# SCH_MR2-reactive-led-system-new-audio-sy.net
KiCad netlist of a schematic drawn in EasyEDA
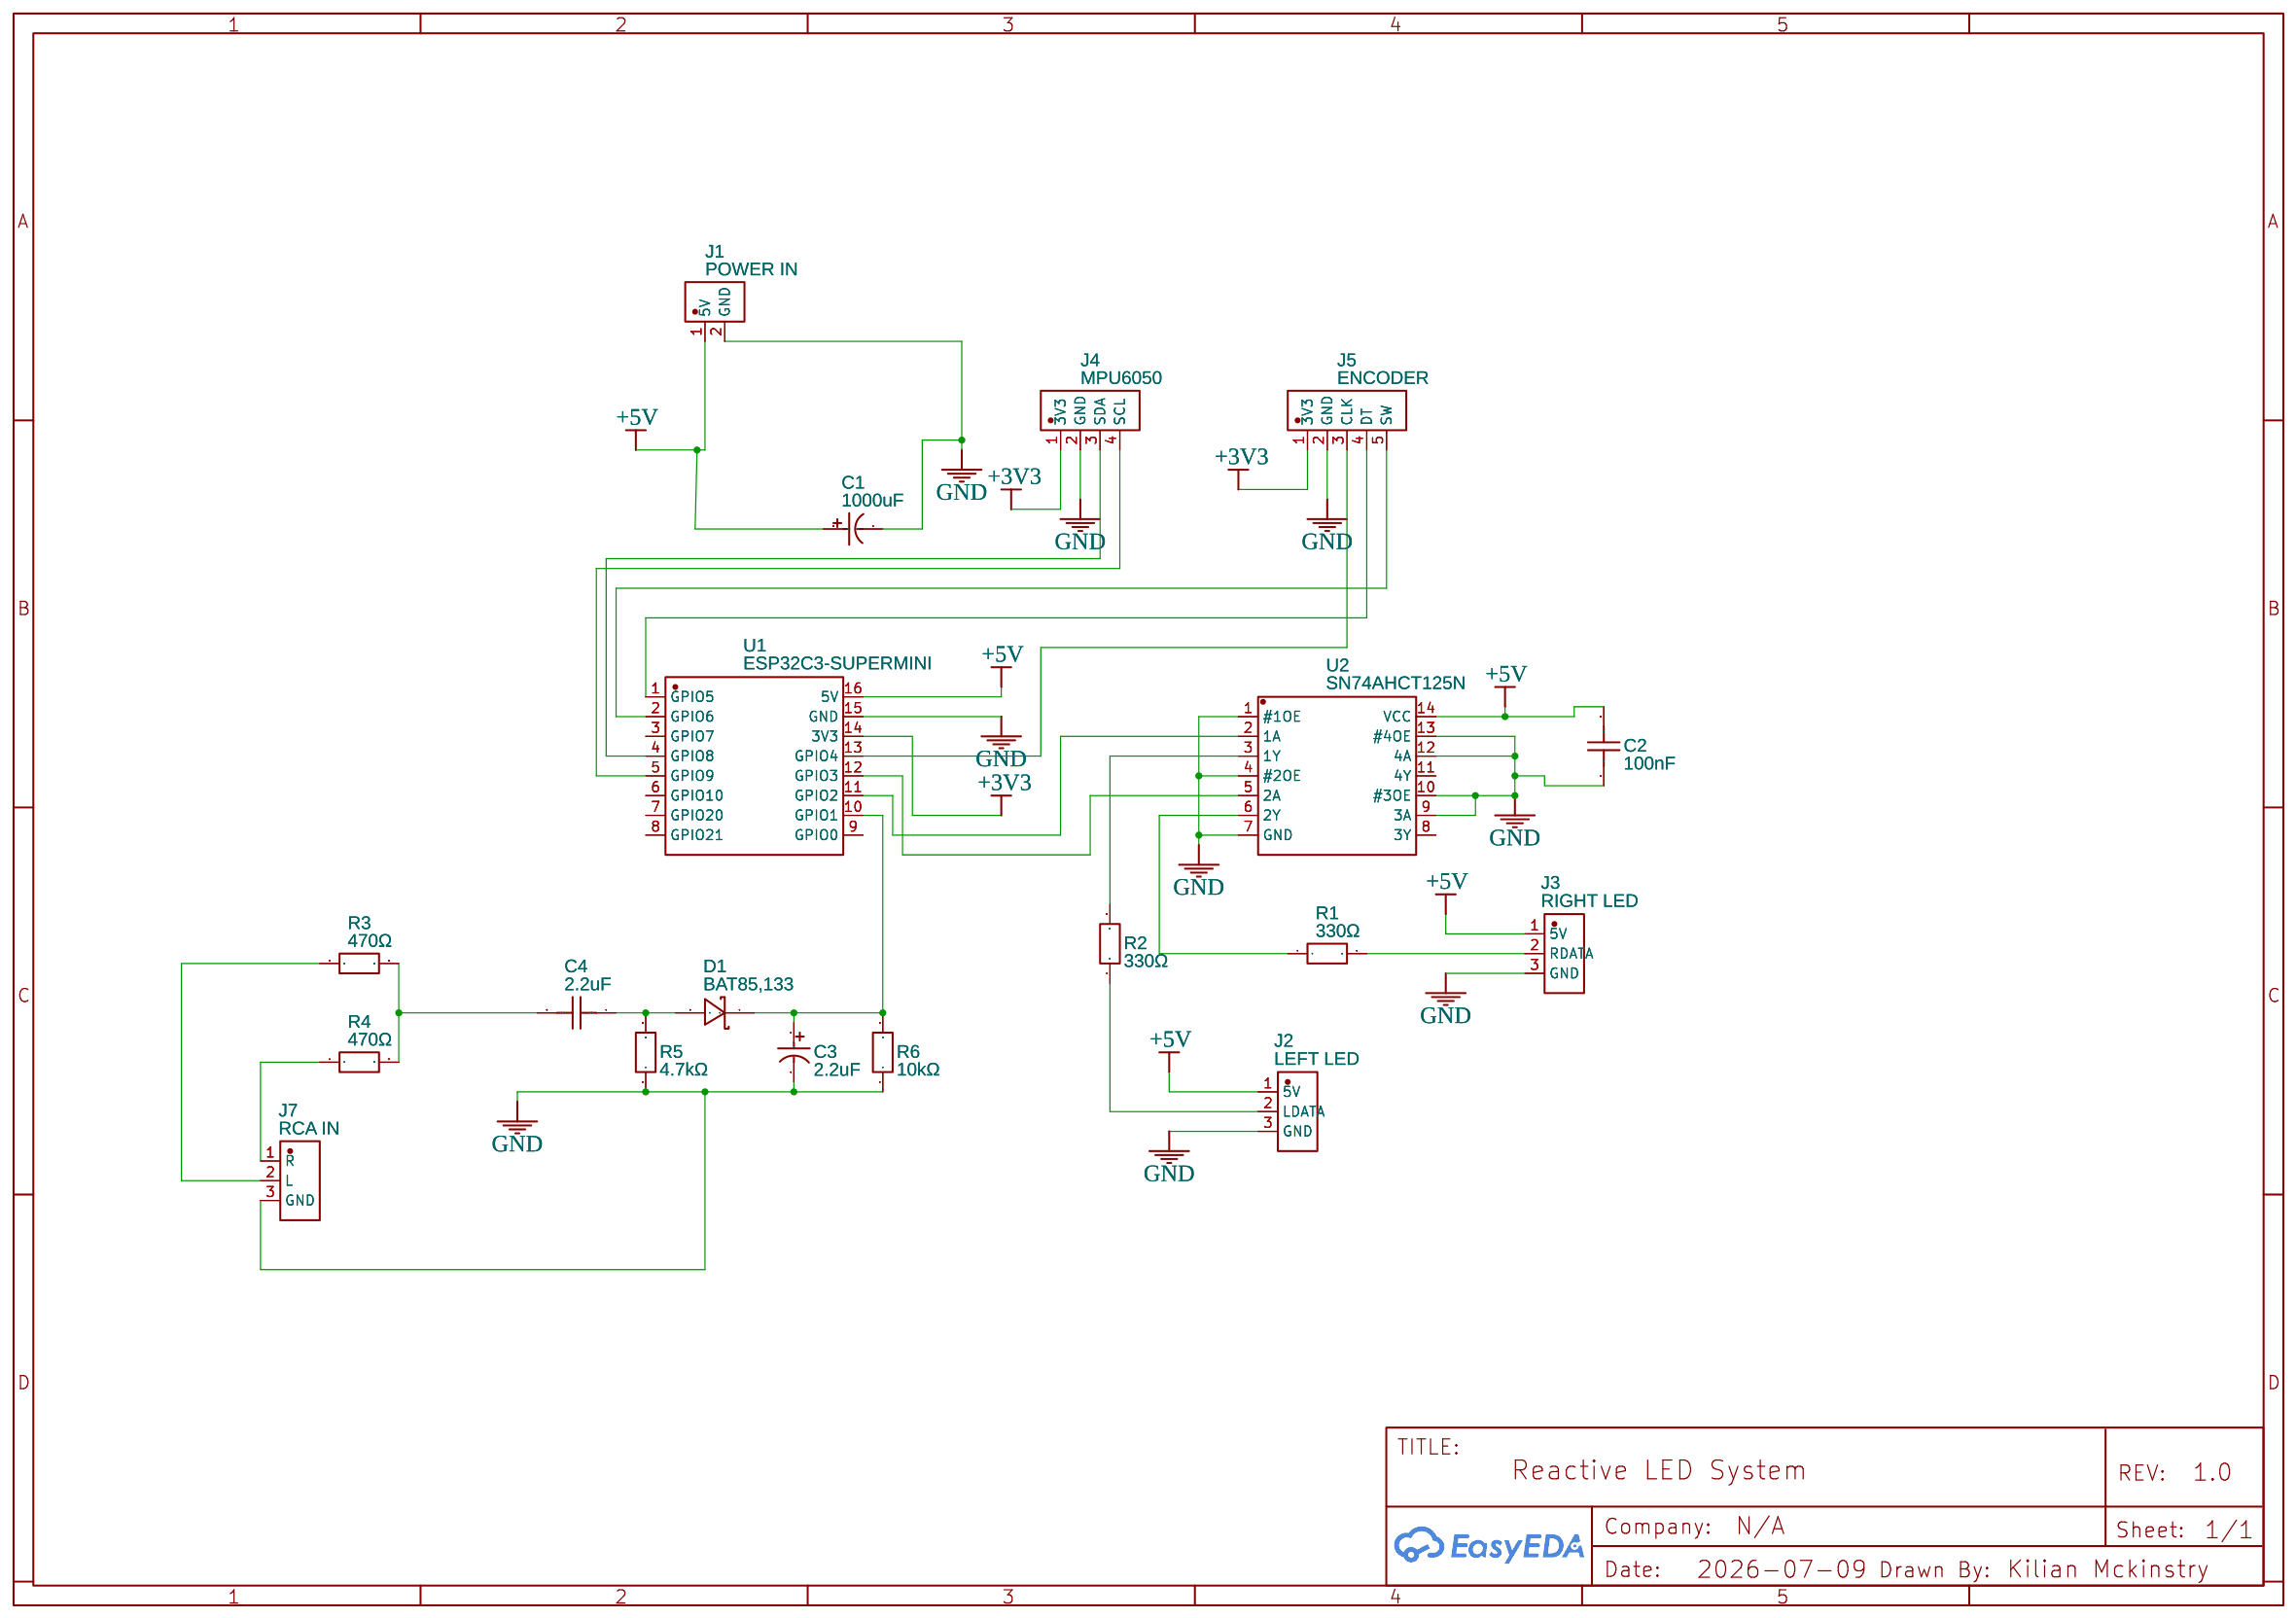
[diagram p0: schematic sheet]

(export (version "E")
  (design (tool "Eeschema 10.0.6"))
  (components
    (comp (ref "C1")
      (value "1000uF")
      (fields
        (field (name "Manufacturer Part") "KS106M050C07RR0VH2FP0")
        (field (name "Manufacturer") "Chengx(承兴)")
      )
      (libsource (lib "") (part "electrolytic capacitor10UF50V_1"))
    )
    (comp (ref "C2")
      (value "100nF")
      (fields
        (field (name "Manufacturer Part") "DCM472K39Y5PL6FJ5A0")
        (field (name "Manufacturer") "SHM(南方宏明)")
      )
      (libsource (lib "") (part "DCM472K39Y5PL6FJ5A0_1"))
    )
    (comp (ref "C3")
      (value "2.2uF")
      (fields
        (field (name "Manufacturer Part") "KS106M050C07RR0VH2FP0")
        (field (name "Manufacturer") "Chengx(承兴)")
      )
      (libsource (lib "") (part "electrolytic capacitor10UF50V"))
    )
    (comp (ref "C4")
      (value "2.2uF")
      (fields
        (field (name "Manufacturer Part") "DCM472K39Y5PL6FJ5A0")
        (field (name "Manufacturer") "SHM(南方宏明)")
      )
      (libsource (lib "") (part "DCM472K39Y5PL6FJ5A0"))
    )
    (comp (ref "D1")
      (value "BAT85,133")
      (fields (field (name "Manufacturer") "Nexperia(安世)"))
      (libsource (lib "") (part "BAT85,133"))
    )
    (comp (ref "J1")
      (value "POWER IN")
      (fields (field (name "Manufacturer Part") "XH2.54-2PIN-直针"))
      (libsource (lib "") (part "XH2.54-2PIN-直针"))
    )
    (comp (ref "J2")
      (value "LEFT LED")
      (fields (field (name "Manufacturer Part") "XH_2.54_3P"))
      (libsource (lib "") (part "XH_2.54_3P_2"))
    )
    (comp (ref "J3")
      (value "RIGHT LED")
      (fields (field (name "Manufacturer Part") "XH_2.54_3P"))
      (libsource (lib "") (part "XH_2.54_3P"))
    )
    (comp (ref "J4")
      (value "MPU6050")
      (fields (field (name "Manufacturer Part") "WAFER-XH254Z-4AL") (field (name "Manufacturer") "HANBO(汉博)"))
      (libsource (lib "") (part "WAFER-XH254Z-4AL"))
    )
    (comp (ref "J5")
      (value "ENCODER")
      (fields (field (name "Manufacturer Part") "XH_2.54_5P"))
      (libsource (lib "") (part "XH_2.54_5P"))
    )
    (comp (ref "J7")
      (value "RCA IN")
      (fields (field (name "Manufacturer Part") "XH_2.54_3P"))
      (libsource (lib "") (part "XH_2.54_3P_1"))
    )
    (comp (ref "R1")
      (value "330Ω")
      (fields (field (name "Manufacturer Part") "CR1/8W-56K±5%-ST52") (field (name "Manufacturer") "VO(翔胜)"))
      (libsource (lib "") (part "CR1/8W-56K±5%-ST52_1"))
    )
    (comp (ref "R2")
      (value "330Ω")
      (fields (field (name "Manufacturer Part") "CR1/8W-56K±5%-ST52") (field (name "Manufacturer") "VO(翔胜)"))
      (libsource (lib "") (part "CR1/8W-56K±5%-ST52"))
    )
    (comp (ref "R3")
      (value "470Ω")
      (fields (field (name "Manufacturer Part") "CR1/8W-56K±5%-ST52") (field (name "Manufacturer") "VO(翔胜)"))
      (libsource (lib "") (part "CR1/8W-56K±5%-ST52_1"))
    )
    (comp (ref "R4")
      (value "470Ω")
      (fields (field (name "Manufacturer Part") "CR1/8W-56K±5%-ST52") (field (name "Manufacturer") "VO(翔胜)"))
      (libsource (lib "") (part "CR1/8W-56K±5%-ST52_1"))
    )
    (comp (ref "R5")
      (value "4.7kΩ")
      (fields (field (name "Manufacturer Part") "CR1/8W-56K±5%-ST52") (field (name "Manufacturer") "VO(翔胜)"))
      (libsource (lib "") (part "CR1/8W-56K±5%-ST52"))
    )
    (comp (ref "R6")
      (value "10kΩ")
      (fields (field (name "Manufacturer Part") "CR1/8W-56K±5%-ST52") (field (name "Manufacturer") "VO(翔胜)"))
      (libsource (lib "") (part "CR1/8W-56K±5%-ST52"))
    )
    (comp (ref "U1")
      (value "ESP32C3-SUPERMINI")
      (fields (field (name "Manufacturer Part") "ESP32C3-SuperMini"))
      (libsource (lib "") (part "ESP32C3-SUPERMINI"))
    )
    (comp (ref "U2")
      (value "SN74AHCT125N")
      (fields (field (name "Manufacturer") "TI(德州仪器)"))
      (libsource (lib "") (part "SN74AHCT125N"))
    )
  )
  (nets
    (net (code "1") (name "+3V3") (class "Default")
      (node (ref "J4") (pin "1") (pinfunction "3V3_1") (pintype "unspecified"))
      (node (ref "J5") (pin "1") (pinfunction "3V3_1") (pintype "unspecified"))
      (node (ref "U1") (pin "14") (pinfunction "3V3_14") (pintype "unspecified"))
    )
    (net (code "2") (name "+5V") (class "Default")
      (node (ref "C1") (pin "1") (pinfunction "+_1") (pintype "input"))
      (node (ref "C2") (pin "2") (pinfunction "2_2") (pintype "unspecified"))
      (node (ref "J1") (pin "1") (pinfunction "5V_1") (pintype "unspecified"))
      (node (ref "J2") (pin "1") (pinfunction "5V_1") (pintype "unspecified"))
      (node (ref "J3") (pin "1") (pinfunction "5V_1") (pintype "unspecified"))
      (node (ref "U1") (pin "16") (pinfunction "5V_16") (pintype "unspecified"))
      (node (ref "U2") (pin "14") (pinfunction "VCC_14") (pintype "unspecified"))
    )
    (net (code "3") (name "GND") (class "Default")
      (node (ref "C1") (pin "2") (pinfunction "-_2") (pintype "input"))
      (node (ref "C2") (pin "1") (pinfunction "1_1") (pintype "unspecified"))
      (node (ref "C3") (pin "2") (pinfunction "-_2") (pintype "input"))
      (node (ref "J1") (pin "2") (pinfunction "GND_2") (pintype "unspecified"))
      (node (ref "J2") (pin "3") (pinfunction "GND_3") (pintype "unspecified"))
      (node (ref "J3") (pin "3") (pinfunction "GND_3") (pintype "unspecified"))
      (node (ref "J4") (pin "2") (pinfunction "GND_2") (pintype "unspecified"))
      (node (ref "J5") (pin "2") (pinfunction "GND_2") (pintype "unspecified"))
      (node (ref "J7") (pin "3") (pinfunction "GND_3") (pintype "unspecified"))
      (node (ref "R5") (pin "1") (pinfunction "1_1") (pintype "unspecified"))
      (node (ref "R6") (pin "1") (pinfunction "1_1") (pintype "unspecified"))
      (node (ref "U1") (pin "15") (pinfunction "GND_15") (pintype "unspecified"))
      (node (ref "U2") (pin "1") (pinfunction "#1OE_1") (pintype "unspecified"))
      (node (ref "U2") (pin "10") (pinfunction "#3OE_10") (pintype "unspecified"))
      (node (ref "U2") (pin "12") (pinfunction "4A_12") (pintype "unspecified"))
      (node (ref "U2") (pin "13") (pinfunction "#4OE_13") (pintype "unspecified"))
      (node (ref "U2") (pin "4") (pinfunction "#2OE_4") (pintype "unspecified"))
      (node (ref "U2") (pin "7") (pinfunction "GND_7") (pintype "unspecified"))
      (node (ref "U2") (pin "9") (pinfunction "3A_9") (pintype "unspecified"))
    )
    (net (code "4") (name "Net-(C3-+)") (class "Default")
      (node (ref "C3") (pin "1") (pinfunction "+_1") (pintype "input"))
      (node (ref "D1") (pin "1") (pinfunction "K_1") (pintype "unspecified"))
      (node (ref "R6") (pin "2") (pinfunction "2_2") (pintype "unspecified"))
      (node (ref "U1") (pin "10") (pinfunction "GPIO1_10") (pintype "unspecified"))
    )
    (net (code "5") (name "Net-(C4-Pad2)") (class "Default")
      (node (ref "C4") (pin "2") (pinfunction "2_2") (pintype "unspecified"))
      (node (ref "R3") (pin "2") (pinfunction "2_2") (pintype "unspecified"))
      (node (ref "R4") (pin "2") (pinfunction "2_2") (pintype "unspecified"))
    )
    (net (code "6") (name "Net-(D1-A)") (class "Default")
      (node (ref "C4") (pin "1") (pinfunction "1_1") (pintype "unspecified"))
      (node (ref "D1") (pin "2") (pinfunction "A_2") (pintype "unspecified"))
      (node (ref "R5") (pin "2") (pinfunction "2_2") (pintype "unspecified"))
    )
    (net (code "7") (name "Net-(J2-LDATA)") (class "Default")
      (node (ref "J2") (pin "2") (pinfunction "LDATA_2") (pintype "unspecified"))
      (node (ref "R2") (pin "1") (pinfunction "1_1") (pintype "unspecified"))
    )
    (net (code "8") (name "Net-(J3-RDATA)") (class "Default")
      (node (ref "J3") (pin "2") (pinfunction "RDATA_2") (pintype "unspecified"))
      (node (ref "R1") (pin "2") (pinfunction "2_2") (pintype "unspecified"))
    )
    (net (code "9") (name "Net-(J4-SCL)") (class "Default")
      (node (ref "J4") (pin "4") (pinfunction "SCL_4") (pintype "unspecified"))
      (node (ref "U1") (pin "5") (pinfunction "GPIO9_5") (pintype "unspecified"))
    )
    (net (code "10") (name "Net-(J4-SDA)") (class "Default")
      (node (ref "J4") (pin "3") (pinfunction "SDA_3") (pintype "unspecified"))
      (node (ref "U1") (pin "4") (pinfunction "GPIO8_4") (pintype "unspecified"))
    )
    (net (code "11") (name "Net-(J5-CLK)") (class "Default")
      (node (ref "J5") (pin "3") (pinfunction "CLK_3") (pintype "unspecified"))
      (node (ref "U1") (pin "13") (pinfunction "GPIO4_13") (pintype "unspecified"))
    )
    (net (code "12") (name "Net-(J5-DT)") (class "Default")
      (node (ref "J5") (pin "4") (pinfunction "DT_4") (pintype "unspecified"))
      (node (ref "U1") (pin "1") (pinfunction "GPIO5_1") (pintype "unspecified"))
    )
    (net (code "13") (name "Net-(J5-SW)") (class "Default")
      (node (ref "J5") (pin "5") (pinfunction "SW_5") (pintype "unspecified"))
      (node (ref "U1") (pin "2") (pinfunction "GPIO6_2") (pintype "unspecified"))
    )
    (net (code "14") (name "Net-(J7-L)") (class "Default")
      (node (ref "J7") (pin "2") (pinfunction "L_2") (pintype "unspecified"))
      (node (ref "R3") (pin "1") (pinfunction "1_1") (pintype "unspecified"))
    )
    (net (code "15") (name "Net-(J7-R)") (class "Default")
      (node (ref "J7") (pin "1") (pinfunction "R_1") (pintype "unspecified"))
      (node (ref "R4") (pin "1") (pinfunction "1_1") (pintype "unspecified"))
    )
    (net (code "16") (name "Net-(U1-GPIO2)") (class "Default")
      (node (ref "U1") (pin "11") (pinfunction "GPIO2_11") (pintype "unspecified"))
      (node (ref "U2") (pin "2") (pinfunction "1A_2") (pintype "unspecified"))
    )
    (net (code "17") (name "Net-(U1-GPIO3)") (class "Default")
      (node (ref "U1") (pin "12") (pinfunction "GPIO3_12") (pintype "unspecified"))
      (node (ref "U2") (pin "5") (pinfunction "2A_5") (pintype "unspecified"))
    )
    (net (code "18") (name "Net-(U2-1Y)") (class "Default")
      (node (ref "R2") (pin "2") (pinfunction "2_2") (pintype "unspecified"))
      (node (ref "U2") (pin "3") (pinfunction "1Y_3") (pintype "unspecified"))
    )
    (net (code "19") (name "Net-(U2-2Y)") (class "Default")
      (node (ref "R1") (pin "1") (pinfunction "1_1") (pintype "unspecified"))
      (node (ref "U2") (pin "6") (pinfunction "2Y_6") (pintype "unspecified"))
    )
    (net (code "20") (name "unconnected-(U1-GPIO0-Pad9)") (class "Default")
      (node (ref "U1") (pin "9") (pinfunction "GPIO0_9") (pintype "unspecified"))
    )
    (net (code "21") (name "unconnected-(U1-GPIO7-Pad3)") (class "Default")
      (node (ref "U1") (pin "3") (pinfunction "GPIO7_3") (pintype "unspecified"))
    )
    (net (code "22") (name "unconnected-(U1-GPIO10-Pad6)") (class "Default")
      (node (ref "U1") (pin "6") (pinfunction "GPIO10_6") (pintype "unspecified"))
    )
    (net (code "23") (name "unconnected-(U1-GPIO20-Pad7)") (class "Default")
      (node (ref "U1") (pin "7") (pinfunction "GPIO20_7") (pintype "unspecified"))
    )
    (net (code "24") (name "unconnected-(U1-GPIO21-Pad8)") (class "Default")
      (node (ref "U1") (pin "8") (pinfunction "GPIO21_8") (pintype "unspecified"))
    )
    (net (code "25") (name "unconnected-(U2-3Y-Pad8)") (class "Default")
      (node (ref "U2") (pin "8") (pinfunction "3Y_8") (pintype "unspecified"))
    )
    (net (code "26") (name "unconnected-(U2-4Y-Pad11)") (class "Default")
      (node (ref "U2") (pin "11") (pinfunction "4Y_11") (pintype "unspecified"))
    )
  )
)
